# PowerSource.net
KiCad netlist of a schematic drawn in Altium Designer
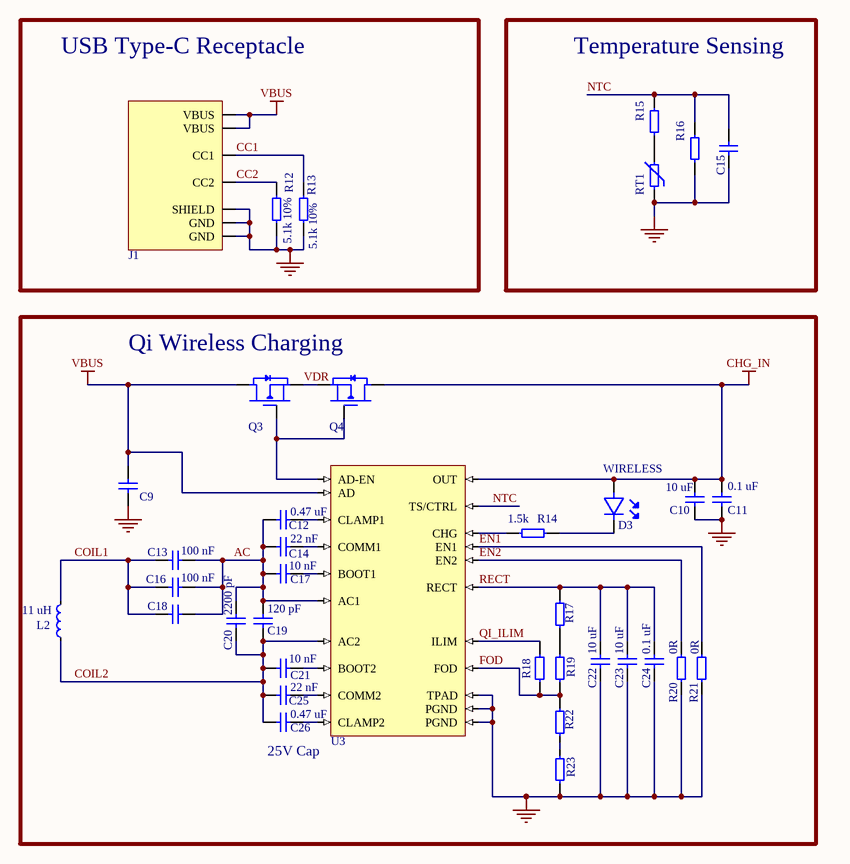
[diagram p0: PowerSource.SchDoc]

(export (version "E")
  (design (tool "Eeschema 10.0.6"))
  (components
    (comp (ref "C9")
      (value "Capacitor")
      (footprint "0603 Capacitor")
      (libsource (lib "MoldsvorLibrary") (part "Capacitor"))
    )
    (comp (ref "C10")
      (value "10 uF")
      (footprint "0603 Capacitor")
      (libsource (lib "MoldsvorLibrary") (part "Capacitor"))
    )
    (comp (ref "C11")
      (value "0.1 uF")
      (footprint "0603 Capacitor")
      (libsource (lib "MoldsvorLibrary") (part "Capacitor"))
    )
    (comp (ref "C12")
      (value "22 nF")
      (footprint "0603 Capacitor")
      (libsource (lib "MoldsvorLibrary") (part "Capacitor"))
    )
    (comp (ref "C13")
      (value "100 nF")
      (footprint "0603 Capacitor")
      (libsource (lib "MoldsvorLibrary") (part "Capacitor"))
    )
    (comp (ref "C14")
      (value "0.47 uF")
      (footprint "0603 Capacitor")
      (libsource (lib "MoldsvorLibrary") (part "Capacitor"))
    )
    (comp (ref "C15")
      (value "Capacitor")
      (footprint "0603 Capacitor")
      (libsource (lib "MoldsvorLibrary") (part "Capacitor"))
    )
    (comp (ref "C16")
      (value "100 nF")
      (footprint "0603 Capacitor")
      (libsource (lib "MoldsvorLibrary") (part "Capacitor"))
    )
    (comp (ref "C17")
      (value "10 nF")
      (footprint "0603 Capacitor")
      (libsource (lib "MoldsvorLibrary") (part "Capacitor"))
    )
    (comp (ref "C18")
      (value "Capacitor")
      (footprint "0603 Capacitor")
      (libsource (lib "MoldsvorLibrary") (part "Capacitor"))
    )
    (comp (ref "C19")
      (value "120 pF")
      (footprint "0603 Capacitor")
      (libsource (lib "MoldsvorLibrary") (part "Capacitor"))
    )
    (comp (ref "C20")
      (value "2200 pF")
      (footprint "0603 Capacitor")
      (libsource (lib "MoldsvorLibrary") (part "Capacitor"))
    )
    (comp (ref "C21")
      (value "10 nF")
      (footprint "0603 Capacitor")
      (libsource (lib "MoldsvorLibrary") (part "Capacitor"))
    )
    (comp (ref "C22")
      (value "10 uF")
      (footprint "0603 Capacitor")
      (libsource (lib "MoldsvorLibrary") (part "Capacitor"))
    )
    (comp (ref "C23")
      (value "10 uF")
      (footprint "0603 Capacitor")
      (libsource (lib "MoldsvorLibrary") (part "Capacitor"))
    )
    (comp (ref "C24")
      (value "0.1 uF")
      (footprint "0603 Capacitor")
      (libsource (lib "MoldsvorLibrary") (part "Capacitor"))
    )
    (comp (ref "C25")
      (value "22 nF")
      (footprint "0603 Capacitor")
      (libsource (lib "MoldsvorLibrary") (part "Capacitor"))
    )
    (comp (ref "C26")
      (value "0.47 uF")
      (footprint "0603 Capacitor")
      (libsource (lib "MoldsvorLibrary") (part "Capacitor"))
    )
    (comp (ref "D3")
      (value "WIRELESS")
      (footprint "0603 LED")
      (libsource (lib "MoldsvorLibrary") (part "LED"))
    )
    (comp (ref "J1")
      (value "USB4125-GF-A")
      (footprint "USB4125")
      (description "Conn Rcp USB2.0 Typ C 24P SMD Ra")
      (libsource (lib "MoldsvorLibrary") (part "USB4125-GF-A"))
    )
    (comp (ref "L2")
      (value "11 uH")
      (footprint "WURTH QI COIL")
      (description "RX 1 COIL 1 LAYER 26UH 1.1A")
      (fields (field (name "TOLERANCE") "10%"))
      (libsource (lib "MoldsvorLibrary") (part "760308101214"))
    )
    (comp (ref "Q3")
      (value "CSD25404Q3")
      (footprint "CSD25404Q3")
      (description "MOSFET P-CH 20V 104A 8VSON")
      (libsource (lib "MoldsvorLibrary") (part "CSD25404Q3"))
    )
    (comp (ref "Q4")
      (value "CSD25404Q3")
      (footprint "CSD25404Q3")
      (description "MOSFET P-CH 20V 104A 8VSON")
      (libsource (lib "MoldsvorLibrary") (part "CSD25404Q3"))
    )
    (comp (ref "R12")
      (value "5.1k 10%")
      (footprint "0603 Resistor")
      (libsource (lib "MoldsvorLibrary") (part "Resistor"))
    )
    (comp (ref "R13")
      (value "5.1k 10%")
      (footprint "0603 Resistor")
      (libsource (lib "MoldsvorLibrary") (part "Resistor"))
    )
    (comp (ref "R14")
      (value "1.5k")
      (footprint "0603 Resistor")
      (libsource (lib "MoldsvorLibrary") (part "Resistor"))
    )
    (comp (ref "R15")
      (value "Resistor")
      (footprint "0603 Resistor")
      (libsource (lib "MoldsvorLibrary") (part "Resistor"))
    )
    (comp (ref "R16")
      (value "Resistor")
      (footprint "0603 Resistor")
      (libsource (lib "MoldsvorLibrary") (part "Resistor"))
    )
    (comp (ref "R17")
      (value "Resistor")
      (footprint "0603 Resistor")
      (libsource (lib "MoldsvorLibrary") (part "Resistor"))
    )
    (comp (ref "R18")
      (value "Resistor")
      (footprint "0603 Resistor")
      (libsource (lib "MoldsvorLibrary") (part "Resistor"))
    )
    (comp (ref "R19")
      (value "Resistor")
      (footprint "0603 Resistor")
      (libsource (lib "MoldsvorLibrary") (part "Resistor"))
    )
    (comp (ref "R20")
      (value "0R")
      (footprint "0603 Resistor")
      (libsource (lib "MoldsvorLibrary") (part "Resistor"))
    )
    (comp (ref "R21")
      (value "0R")
      (footprint "0603 Resistor")
      (libsource (lib "MoldsvorLibrary") (part "Resistor"))
    )
    (comp (ref "R22")
      (value "Resistor")
      (footprint "0603 Resistor")
      (libsource (lib "MoldsvorLibrary") (part "Resistor"))
    )
    (comp (ref "R23")
      (value "Resistor")
      (footprint "0603 Resistor")
      (libsource (lib "MoldsvorLibrary") (part "Resistor"))
    )
    (comp (ref "RT1")
      (value "ERT-J1VG103JA")
      (footprint "0603 Resistor")
      (description "Thermistor NTC 10KOhm 5% 2-Pin 0603 Punched Carrier T/R")
      (fields (field (name "TOLERANCE") "5%"))
      (libsource (lib "MoldsvorLibrary") (part "ERT-J1VG103JA"))
    )
    (comp (ref "U3")
      (value "BQ51013BRHLR")
      (footprint "BQ51013B")
      (description "TEXAS INSTRUMENTS - BQ51013BRHLR - WIRELESS POWER SUPPLY RECEIVER, VQFN-20")
      (libsource (lib "MoldsvorBatteryLibrary") (part "BQ51013BRHLR"))
    )
  )
  (nets
    (net (code "1") (name "/AC") (class "Default")
      (node (ref "C12") (pin "1") (pinfunction "1_1") (pintype "passive"))
      (node (ref "C13") (pin "2") (pinfunction "2_2") (pintype "passive"))
      (node (ref "C14") (pin "1") (pinfunction "1_1") (pintype "passive"))
      (node (ref "C16") (pin "1") (pinfunction "1_1") (pintype "passive"))
      (node (ref "C17") (pin "1") (pinfunction "1_1") (pintype "passive"))
      (node (ref "C18") (pin "1") (pinfunction "1_1") (pintype "passive"))
      (node (ref "C19") (pin "2") (pinfunction "2_2") (pintype "passive"))
      (node (ref "C20") (pin "2") (pinfunction "2_2") (pintype "passive"))
      (node (ref "U3") (pin "2") (pinfunction "AC1_2") (pintype "input"))
    )
    (net (code "2") (name "/CC1") (class "Default")
      (node (ref "J1") (pin "A5") (pinfunction "CC1_A5") (pintype "passive"))
      (node (ref "R13") (pin "2") (pintype "passive"))
    )
    (net (code "3") (name "/CC2") (class "Default")
      (node (ref "J1") (pin "B5") (pinfunction "CC2_B5") (pintype "passive"))
      (node (ref "R12") (pin "2") (pintype "passive"))
    )
    (net (code "4") (name "/COIL1") (class "Default")
      (node (ref "C13") (pin "1") (pinfunction "1_1") (pintype "passive"))
      (node (ref "C16") (pin "2") (pinfunction "2_2") (pintype "passive"))
      (node (ref "C18") (pin "2") (pinfunction "2_2") (pintype "passive"))
      (node (ref "L2") (pin "2") (pinfunction "2_2") (pintype "passive"))
    )
    (net (code "5") (name "/COIL2") (class "Default")
      (node (ref "C19") (pin "1") (pinfunction "1_1") (pintype "passive"))
      (node (ref "C20") (pin "1") (pinfunction "1_1") (pintype "passive"))
      (node (ref "C21") (pin "1") (pinfunction "1_1") (pintype "passive"))
      (node (ref "C25") (pin "1") (pinfunction "1_1") (pintype "passive"))
      (node (ref "C26") (pin "1") (pinfunction "1_1") (pintype "passive"))
      (node (ref "L2") (pin "1") (pinfunction "1_1") (pintype "passive"))
      (node (ref "U3") (pin "19") (pinfunction "AC2_19") (pintype "input"))
    )
    (net (code "6") (name "/EN1") (class "Default")
      (node (ref "R21") (pin "2") (pintype "passive"))
      (node (ref "U3") (pin "10") (pinfunction "EN1_10") (pintype "input"))
    )
    (net (code "7") (name "/EN2") (class "Default")
      (node (ref "R20") (pin "2") (pintype "passive"))
      (node (ref "U3") (pin "11") (pinfunction "EN2_11") (pintype "input"))
    )
    (net (code "8") (name "/FOD") (class "Default")
      (node (ref "R18") (pin "2") (pintype "passive"))
      (node (ref "R19") (pin "1") (pintype "passive"))
      (node (ref "R22") (pin "2") (pintype "passive"))
      (node (ref "U3") (pin "14") (pinfunction "FOD_14") (pintype "input"))
    )
    (net (code "9") (name "/NTC") (class "Default")
      (node (ref "C15") (pin "2") (pinfunction "2_2") (pintype "passive"))
      (node (ref "R15") (pin "2") (pintype "passive"))
      (node (ref "R16") (pin "2") (pintype "passive"))
      (node (ref "U3") (pin "13") (pinfunction "TS/CTRL_13") (pintype "input"))
    )
    (net (code "10") (name "/QI_ILIM") (class "Default")
      (node (ref "R18") (pin "1") (pintype "passive"))
      (node (ref "U3") (pin "12") (pinfunction "ILIM_12") (pintype "input"))
    )
    (net (code "11") (name "/RECT") (class "Default")
      (node (ref "C22") (pin "2") (pinfunction "2_2") (pintype "passive"))
      (node (ref "C23") (pin "2") (pinfunction "2_2") (pintype "passive"))
      (node (ref "C24") (pin "2") (pinfunction "2_2") (pintype "passive"))
      (node (ref "R17") (pin "1") (pintype "passive"))
      (node (ref "U3") (pin "18") (pinfunction "RECT_18") (pintype "input"))
    )
    (net (code "12") (name "/VDR") (class "Default")
      (node (ref "Q3") (pin "5") (pinfunction "5_5") (pintype "passive"))
      (node (ref "Q4") (pin "5") (pinfunction "5_5") (pintype "passive"))
    )
    (net (code "13") (name "CHG_IN") (class "Default")
      (node (ref "C10") (pin "2") (pinfunction "2_2") (pintype "passive"))
      (node (ref "C11") (pin "2") (pinfunction "2_2") (pintype "passive"))
      (node (ref "D3") (pin "1") (pintype "passive"))
      (node (ref "Q4") (pin "1") (pinfunction "1_1") (pintype "passive"))
      (node (ref "U3") (pin "4") (pinfunction "OUT_4") (pintype "input"))
    )
    (net (code "14") (name "GND") (class "Default")
      (node (ref "C10") (pin "1") (pinfunction "1_1") (pintype "passive"))
      (node (ref "C11") (pin "1") (pinfunction "1_1") (pintype "passive"))
      (node (ref "C15") (pin "1") (pinfunction "1_1") (pintype "passive"))
      (node (ref "C22") (pin "1") (pinfunction "1_1") (pintype "passive"))
      (node (ref "C23") (pin "1") (pinfunction "1_1") (pintype "passive"))
      (node (ref "C24") (pin "1") (pinfunction "1_1") (pintype "passive"))
      (node (ref "C9") (pin "1") (pinfunction "1_1") (pintype "passive"))
      (node (ref "J1") (pin "A12") (pinfunction "GND_A12") (pintype "passive"))
      (node (ref "J1") (pin "B12") (pinfunction "GND_B12") (pintype "passive"))
      (node (ref "J1") (pin "SHIELD") (pinfunction "SHIELD_SHIELD") (pintype "passive"))
      (node (ref "R12") (pin "1") (pintype "passive"))
      (node (ref "R13") (pin "1") (pintype "passive"))
      (node (ref "R16") (pin "1") (pintype "passive"))
      (node (ref "R20") (pin "1") (pintype "passive"))
      (node (ref "R21") (pin "1") (pintype "passive"))
      (node (ref "R23") (pin "1") (pintype "passive"))
      (node (ref "RT1") (pin "1") (pintype "passive"))
      (node (ref "U3") (pin "1") (pinfunction "PGND_1") (pintype "input"))
      (node (ref "U3") (pin "20") (pinfunction "PGND_20") (pintype "input"))
      (node (ref "U3") (pin "21") (pinfunction "TPAD_21") (pintype "input"))
    )
    (net (code "15") (name "Net-(D3-Pad2)") (class "Default")
      (node (ref "D3") (pin "2") (pintype "passive"))
      (node (ref "R14") (pin "2") (pintype "passive"))
    )
    (net (code "16") (name "Net-(R15-Pad1)") (class "Default")
      (node (ref "R15") (pin "1") (pintype "passive"))
      (node (ref "RT1") (pin "2") (pintype "passive"))
    )
    (net (code "17") (name "Net-(R17-Pad2)") (class "Default")
      (node (ref "R17") (pin "2") (pintype "passive"))
      (node (ref "R19") (pin "2") (pintype "passive"))
    )
    (net (code "18") (name "Net-(R22-Pad1)") (class "Default")
      (node (ref "R22") (pin "1") (pintype "passive"))
      (node (ref "R23") (pin "2") (pintype "passive"))
    )
    (net (code "19") (name "Net-(U3-AD-EN)") (class "Default")
      (node (ref "Q3") (pin "4") (pinfunction "4_4") (pintype "passive"))
      (node (ref "Q4") (pin "4") (pinfunction "4_4") (pintype "passive"))
      (node (ref "U3") (pin "8") (pinfunction "AD-EN_8") (pintype "input"))
    )
    (net (code "20") (name "Net-(U3-BOOT1)") (class "Default")
      (node (ref "C17") (pin "2") (pinfunction "2_2") (pintype "passive"))
      (node (ref "U3") (pin "3") (pinfunction "BOOT1_3") (pintype "input"))
    )
    (net (code "21") (name "Net-(U3-BOOT2)") (class "Default")
      (node (ref "C21") (pin "2") (pinfunction "2_2") (pintype "passive"))
      (node (ref "U3") (pin "17") (pinfunction "BOOT2_17") (pintype "input"))
    )
    (net (code "22") (name "Net-(U3-CHG)") (class "Default")
      (node (ref "R14") (pin "1") (pintype "passive"))
      (node (ref "U3") (pin "7") (pinfunction "CHG_7") (pintype "input"))
    )
    (net (code "23") (name "Net-(U3-CLAMP1)") (class "Default")
      (node (ref "C14") (pin "2") (pinfunction "2_2") (pintype "passive"))
      (node (ref "U3") (pin "5") (pinfunction "CLAMP1_5") (pintype "input"))
    )
    (net (code "24") (name "Net-(U3-CLAMP2)") (class "Default")
      (node (ref "C26") (pin "2") (pinfunction "2_2") (pintype "passive"))
      (node (ref "U3") (pin "16") (pinfunction "CLAMP2_16") (pintype "input"))
    )
    (net (code "25") (name "Net-(U3-COMM1)") (class "Default")
      (node (ref "C12") (pin "2") (pinfunction "2_2") (pintype "passive"))
      (node (ref "U3") (pin "6") (pinfunction "COMM1_6") (pintype "input"))
    )
    (net (code "26") (name "Net-(U3-COMM2)") (class "Default")
      (node (ref "C25") (pin "2") (pinfunction "2_2") (pintype "passive"))
      (node (ref "U3") (pin "15") (pinfunction "COMM2_15") (pintype "input"))
    )
    (net (code "27") (name "VBUS") (class "Default")
      (node (ref "C9") (pin "2") (pinfunction "2_2") (pintype "passive"))
      (node (ref "J1") (pin "A9") (pinfunction "VBUS_A9") (pintype "passive"))
      (node (ref "J1") (pin "B9") (pinfunction "VBUS_B9") (pintype "passive"))
      (node (ref "Q3") (pin "1") (pinfunction "1_1") (pintype "passive"))
      (node (ref "U3") (pin "9") (pinfunction "AD_9") (pintype "input"))
    )
  )
)
